# Photodiode.net
KiCad netlist of a schematic drawn in Altium Designer
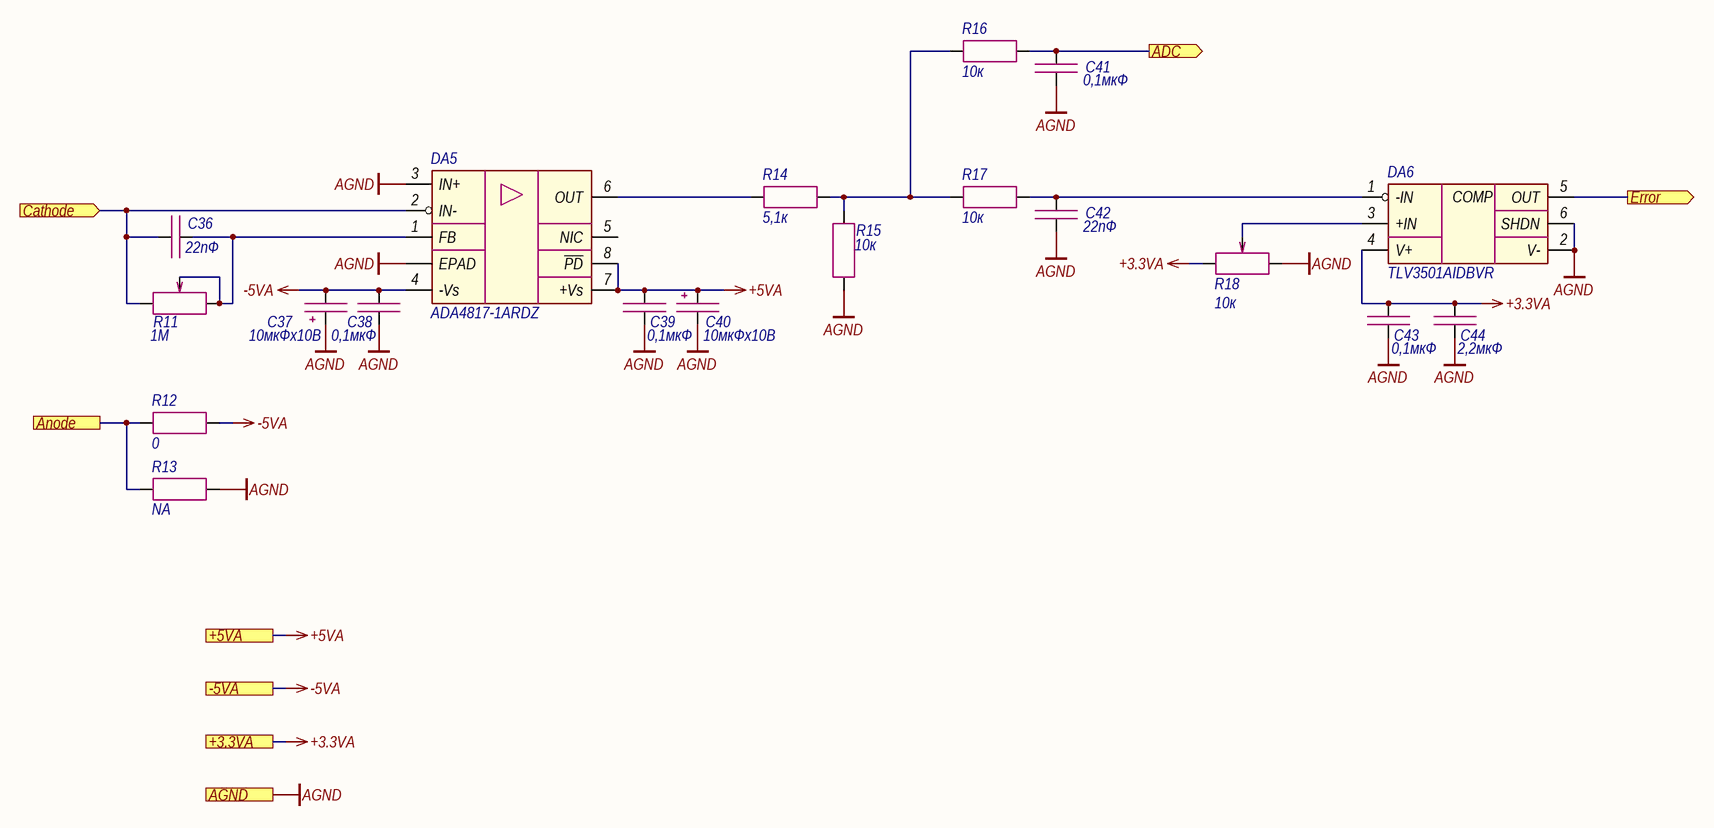
[diagram p0: Photodiode.SchDoc]

(export (version "E")
  (design (tool "Eeschema 10.0.6"))
  (components
    (comp (ref "C36")
      (value "22пФ")
      (footprint "Pcb_library:CAP_0603")
      (fields (field (name "MANUFACTURER") "Murata"))
      (libsource (lib "Schem_library") (part "Capacitor"))
    )
    (comp (ref "C37")
      (value "10мкФх10B")
      (footprint "Pcb_library:CAP_A")
      (libsource (lib "Schem_library") (part "Capacitor_Polar"))
    )
    (comp (ref "C38")
      (value "0,1мкФ")
      (footprint "Pcb_library:CAP_0603")
      (fields (field (name "MANUFACTURER") "Murata"))
      (libsource (lib "Schem_library") (part "Capacitor"))
    )
    (comp (ref "C39")
      (value "0,1мкФ")
      (footprint "Pcb_library:CAP_0603")
      (fields (field (name "MANUFACTURER") "Murata"))
      (libsource (lib "Schem_library") (part "Capacitor"))
    )
    (comp (ref "C40")
      (value "10мкФх10B")
      (footprint "Pcb_library:CAP_A")
      (libsource (lib "Schem_library") (part "Capacitor_Polar"))
    )
    (comp (ref "C41")
      (value "0,1мкФ")
      (footprint "Pcb_library:CAP_0603")
      (fields (field (name "MANUFACTURER") "Murata"))
      (libsource (lib "Schem_library") (part "Capacitor"))
    )
    (comp (ref "C42")
      (value "22пФ")
      (footprint "Pcb_library:CAP_0603")
      (fields (field (name "MANUFACTURER") "Murata"))
      (libsource (lib "Schem_library") (part "Capacitor"))
    )
    (comp (ref "C43")
      (value "0,1мкФ")
      (footprint "Pcb_library:CAP_0603")
      (fields (field (name "MANUFACTURER") "Murata"))
      (libsource (lib "Schem_library") (part "Capacitor"))
    )
    (comp (ref "C44")
      (value "2,2мкФ")
      (footprint "Pcb_library:CAP_0603")
      (fields (field (name "MANUFACTURER") "Murata"))
      (libsource (lib "Schem_library") (part "Capacitor"))
    )
    (comp (ref "DA5")
      (value "ADA4817-1ARDZ")
      (footprint "Pcb_library:SOIC-8 EPAD")
      (fields (field (name "MANUFACTURER") "Analog Devices"))
      (libsource (lib "Schem_library") (part "ADA4817-1ARDZ"))
    )
    (comp (ref "DA6")
      (value "TLV3501AIDBVR")
      (footprint "Pcb_library:SOT-23-6")
      (fields (field (name "MANUFACTURER") "Texas Instruments"))
      (libsource (lib "Schem_library") (part "TLV3501"))
    )
    (comp (ref "R11")
      (value "1М")
      (footprint "Pcb_library:3224W")
      (fields (field (name "MANUFACTURER") "Bourns"))
      (libsource (lib "Schem_library") (part "Resistor_Variable"))
    )
    (comp (ref "R12")
      (value "0")
      (footprint "Pcb_library:RES_0603")
      (fields (field (name "MANUFACTURER") "Yageo"))
      (libsource (lib "Schem_library") (part "Resistor"))
    )
    (comp (ref "R13")
      (value "NA")
      (footprint "Pcb_library:RES_0603")
      (libsource (lib "Schem_library") (part "Resistor"))
    )
    (comp (ref "R14")
      (value "5,1к")
      (footprint "Pcb_library:RES_0603")
      (fields (field (name "MANUFACTURER") "Yageo"))
      (libsource (lib "Schem_library") (part "Resistor"))
    )
    (comp (ref "R15")
      (value "10к")
      (footprint "Pcb_library:RES_0603")
      (fields (field (name "MANUFACTURER") "Yageo"))
      (libsource (lib "Schem_library") (part "Resistor"))
    )
    (comp (ref "R16")
      (value "10к")
      (footprint "Pcb_library:RES_0603")
      (fields (field (name "MANUFACTURER") "Yageo"))
      (libsource (lib "Schem_library") (part "Resistor"))
    )
    (comp (ref "R17")
      (value "10к")
      (footprint "Pcb_library:RES_0603")
      (fields (field (name "MANUFACTURER") "Yageo"))
      (libsource (lib "Schem_library") (part "Resistor"))
    )
    (comp (ref "R18")
      (value "10к")
      (footprint "Pcb_library:3224W")
      (fields (field (name "MANUFACTURER") "Bourns"))
      (libsource (lib "Schem_library") (part "Resistor_Variable"))
    )
  )
  (nets
    (net (code "1") (name "+3.3VA") (class "Default")
      (node (ref "C43") (pin "1") (pinfunction "1_1") (pintype "passive"))
      (node (ref "C44") (pin "1") (pinfunction "1_1") (pintype "passive"))
      (node (ref "DA6") (pin "4") (pinfunction "V+_4") (pintype "passive"))
      (node (ref "R18") (pin "3") (pintype "passive"))
    )
    (net (code "2") (name "+5VA") (class "Default")
      (node (ref "C39") (pin "1") (pinfunction "1_1") (pintype "passive"))
      (node (ref "C40") (pin "1") (pinfunction "1_1") (pintype "passive"))
      (node (ref "DA5") (pin "7") (pinfunction "+Vs_7") (pintype "passive"))
      (node (ref "DA5") (pin "8") (pinfunction "~{PD}_8") (pintype "passive"))
    )
    (net (code "3") (name "-5VA") (class "Default")
      (node (ref "C37") (pin "2") (pinfunction "2_2") (pintype "passive"))
      (node (ref "C38") (pin "1") (pinfunction "1_1") (pintype "passive"))
      (node (ref "DA5") (pin "4") (pinfunction "-Vs_4") (pintype "passive"))
      (node (ref "R12") (pin "1") (pinfunction "1_1") (pintype "passive"))
    )
    (net (code "4") (name "/ADC") (class "Default")
      (node (ref "C41") (pin "1") (pinfunction "1_1") (pintype "passive"))
      (node (ref "R16") (pin "2") (pinfunction "2_2") (pintype "passive"))
    )
    (net (code "5") (name "/Anode") (class "Default")
      (node (ref "R12") (pin "2") (pinfunction "2_2") (pintype "passive"))
      (node (ref "R13") (pin "1") (pinfunction "1_1") (pintype "passive"))
    )
    (net (code "6") (name "/Cathode") (class "Default")
      (node (ref "C36") (pin "2") (pinfunction "2_2") (pintype "passive"))
      (node (ref "DA5") (pin "2") (pinfunction "IN-_2") (pintype "passive"))
      (node (ref "R11") (pin "1") (pintype "passive"))
    )
    (net (code "7") (name "/Error") (class "Default")
      (node (ref "DA6") (pin "5") (pinfunction "OUT_5") (pintype "passive"))
    )
    (net (code "8") (name "AGND") (class "Default")
      (node (ref "C37") (pin "1") (pinfunction "1_1") (pintype "passive"))
      (node (ref "C38") (pin "2") (pinfunction "2_2") (pintype "passive"))
      (node (ref "C39") (pin "2") (pinfunction "2_2") (pintype "passive"))
      (node (ref "C40") (pin "2") (pinfunction "2_2") (pintype "passive"))
      (node (ref "C41") (pin "2") (pinfunction "2_2") (pintype "passive"))
      (node (ref "C42") (pin "2") (pinfunction "2_2") (pintype "passive"))
      (node (ref "C43") (pin "2") (pinfunction "2_2") (pintype "passive"))
      (node (ref "C44") (pin "2") (pinfunction "2_2") (pintype "passive"))
      (node (ref "DA5") (pin "3") (pinfunction "IN+_3") (pintype "passive"))
      (node (ref "DA5") (pin "EPAD") (pinfunction "EPAD_EPAD") (pintype "passive"))
      (node (ref "DA6") (pin "2") (pinfunction "V-_2") (pintype "passive"))
      (node (ref "DA6") (pin "6") (pinfunction "SHDN_6") (pintype "passive"))
      (node (ref "R13") (pin "2") (pinfunction "2_2") (pintype "passive"))
      (node (ref "R15") (pin "2") (pinfunction "2_2") (pintype "passive"))
      (node (ref "R18") (pin "1") (pintype "passive"))
    )
    (net (code "9") (name "Net-(DA5-FB)") (class "Default")
      (node (ref "C36") (pin "1") (pinfunction "1_1") (pintype "passive"))
      (node (ref "DA5") (pin "1") (pinfunction "FB_1") (pintype "passive"))
      (node (ref "R11") (pin "2") (pintype "passive"))
      (node (ref "R11") (pin "3") (pintype "passive"))
    )
    (net (code "10") (name "Net-(DA5-OUT)") (class "Default")
      (node (ref "DA5") (pin "6") (pinfunction "OUT_6") (pintype "passive"))
      (node (ref "R14") (pin "1") (pinfunction "1_1") (pintype "passive"))
    )
    (net (code "11") (name "Net-(DA6-+IN)") (class "Default")
      (node (ref "DA6") (pin "3") (pinfunction "+IN_3") (pintype "passive"))
      (node (ref "R18") (pin "2") (pintype "passive"))
    )
    (net (code "12") (name "Net-(DA6--IN)") (class "Default")
      (node (ref "C42") (pin "1") (pinfunction "1_1") (pintype "passive"))
      (node (ref "DA6") (pin "1") (pinfunction "-IN_1") (pintype "passive"))
      (node (ref "R17") (pin "2") (pinfunction "2_2") (pintype "passive"))
    )
    (net (code "13") (name "Net-(R14-Pad2)") (class "Default")
      (node (ref "R14") (pin "2") (pinfunction "2_2") (pintype "passive"))
      (node (ref "R15") (pin "1") (pinfunction "1_1") (pintype "passive"))
      (node (ref "R16") (pin "1") (pinfunction "1_1") (pintype "passive"))
      (node (ref "R17") (pin "1") (pinfunction "1_1") (pintype "passive"))
    )
    (net (code "14") (name "unconnected-(DA5-NIC-Pad5)") (class "Default")
      (node (ref "DA5") (pin "5") (pinfunction "NIC_5") (pintype "passive"))
    )
  )
)
